# STM32F030.net
KiCad netlist of a schematic drawn in EAGLE
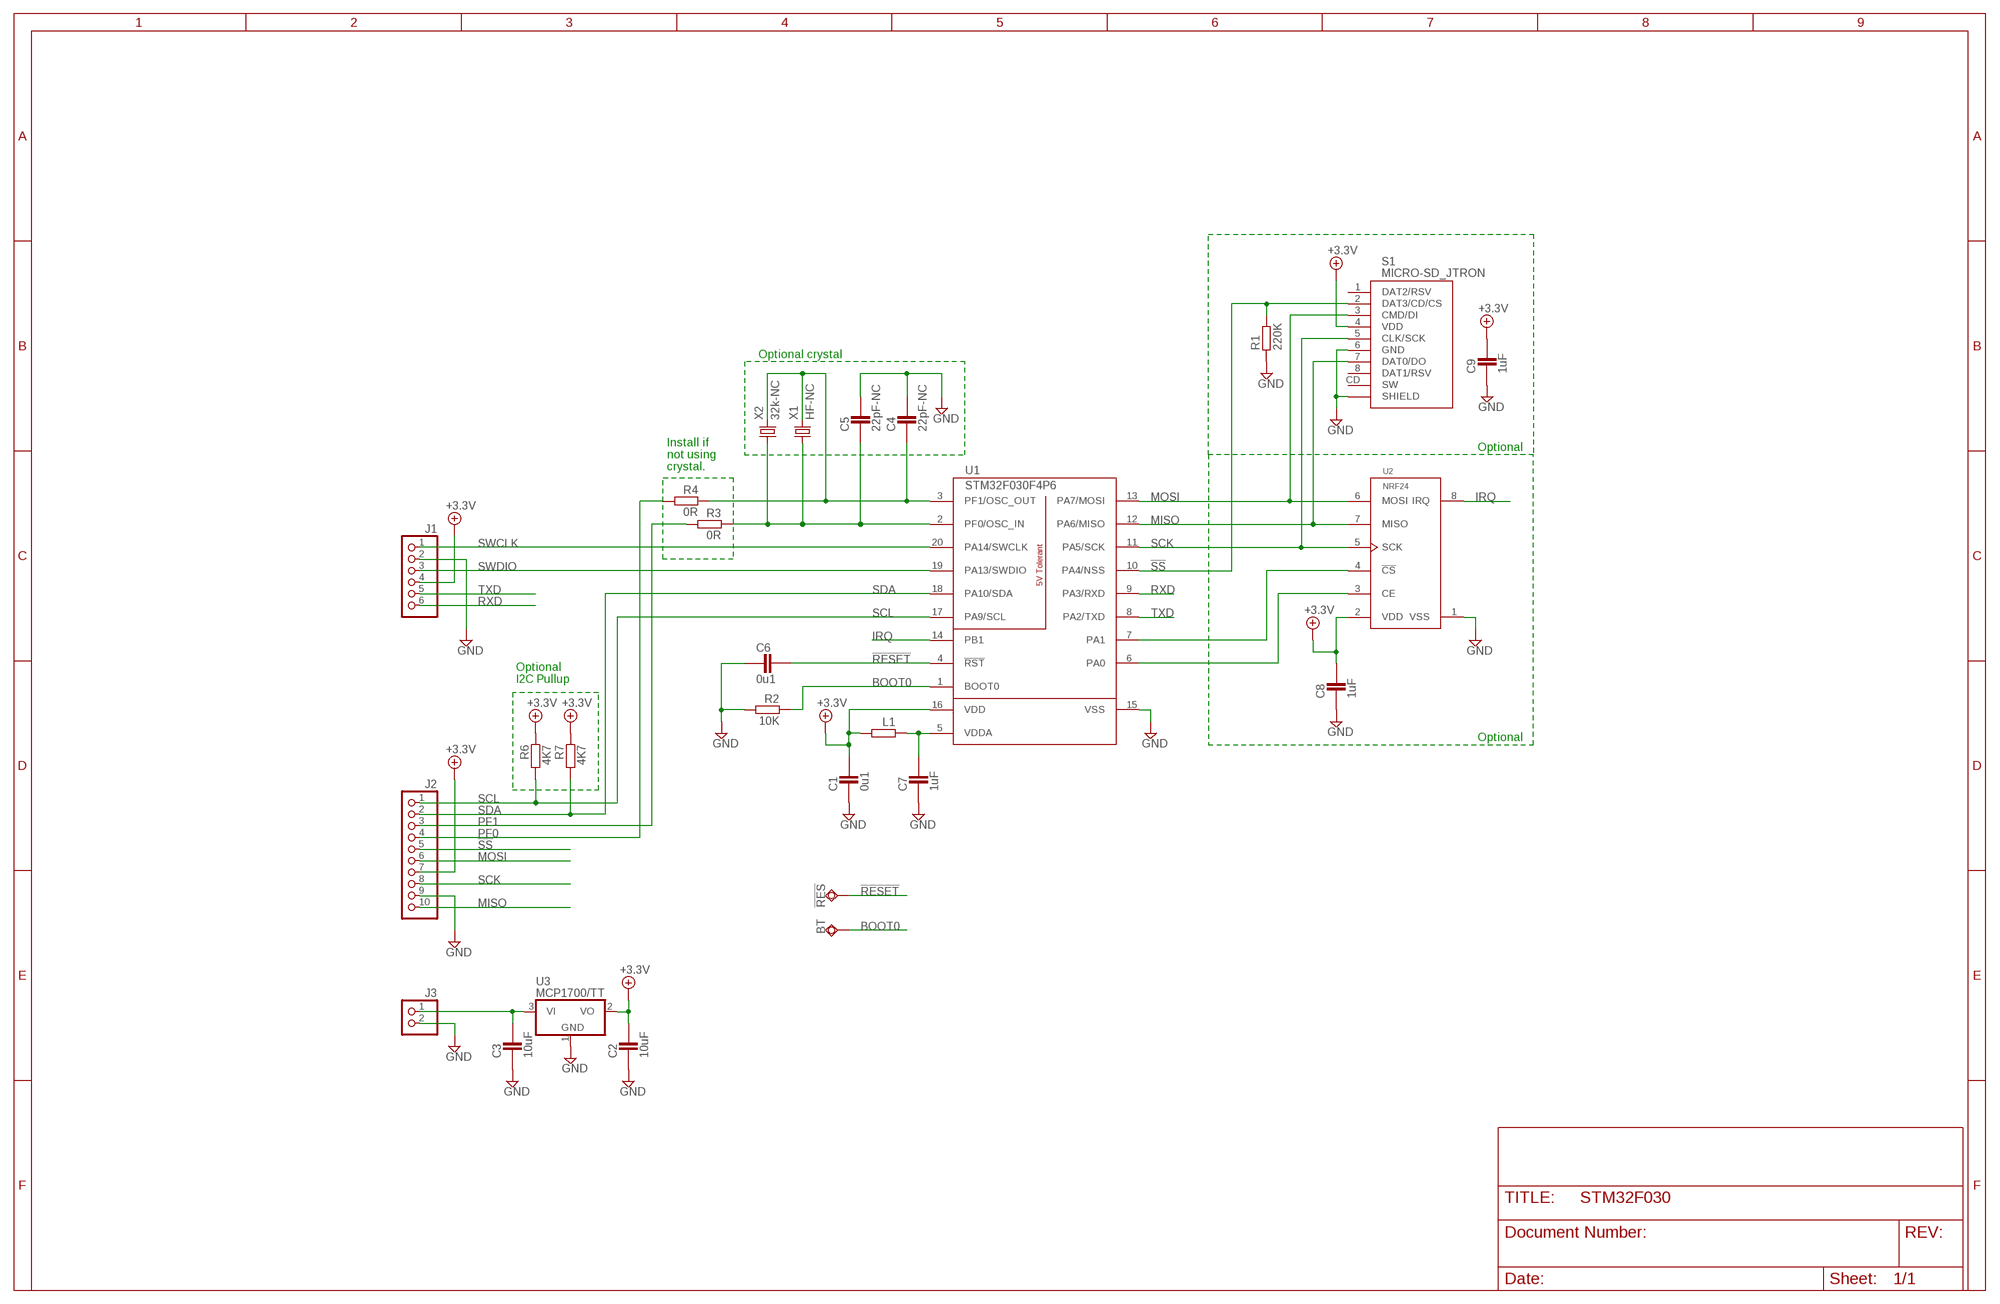
[diagram p0: schematic, sheet 1]

(export (version "E")
  (design (tool "Eeschema 10.0.6"))
  (components
    (comp (ref "!RES")
      (value "TPSQTP08SQ")
      (footprint "eagle-import:TP08SQ")
      (libsource (lib "eagle-import") (part "TPSQTP08SQ"))
    )
    (comp (ref "BT")
      (value "TPSQTP08SQ")
      (footprint "eagle-import:TP08SQ")
      (libsource (lib "eagle-import") (part "TPSQTP08SQ"))
    )
    (comp (ref "C1")
      (value "0u1")
      (footprint "eagle-import:CAPC1608X92N")
      (libsource (lib "eagle-import") (part "CAPACITOR_0603"))
    )
    (comp (ref "C2")
      (value "10uF")
      (footprint "eagle-import:CAPC2012X145AN")
      (libsource (lib "eagle-import") (part "CAPACITOR_0805"))
    )
    (comp (ref "C3")
      (value "10uF")
      (footprint "eagle-import:CAPC2012X145AN")
      (libsource (lib "eagle-import") (part "CAPACITOR_0805"))
    )
    (comp (ref "C4")
      (value "22pF-NC")
      (footprint "eagle-import:CAPC1608X92N")
      (libsource (lib "eagle-import") (part "CAPACITOR_0603"))
    )
    (comp (ref "C5")
      (value "22pF-NC")
      (footprint "eagle-import:CAPC1608X92N")
      (libsource (lib "eagle-import") (part "CAPACITOR_0603"))
    )
    (comp (ref "C6")
      (value "0u1")
      (footprint "eagle-import:CAPC1608X92N")
      (libsource (lib "eagle-import") (part "CAPACITOR_0603"))
    )
    (comp (ref "C7")
      (value "1uF")
      (footprint "eagle-import:CAPC1608X92N")
      (libsource (lib "eagle-import") (part "CAPACITOR_0603"))
    )
    (comp (ref "C8")
      (value "1uF")
      (footprint "eagle-import:CAPC1608X92N")
      (libsource (lib "eagle-import") (part "CAPACITOR_0603"))
    )
    (comp (ref "C9")
      (value "1uF")
      (footprint "eagle-import:CAPC1608X92N")
      (libsource (lib "eagle-import") (part "CAPACITOR_0603"))
    )
    (comp (ref "J1")
      (value "PINHD-1X6")
      (footprint "eagle-import:1X06")
      (libsource (lib "eagle-import") (part "PINHD-1X6"))
    )
    (comp (ref "J2")
      (value "PINHD-1X10")
      (footprint "eagle-import:1X10")
      (libsource (lib "eagle-import") (part "PINHD-1X10"))
    )
    (comp (ref "J3")
      (value "PINHD-1X2_2.54")
      (footprint "eagle-import:1X02")
      (libsource (lib "eagle-import") (part "PINHD-1X2_2.54"))
    )
    (comp (ref "L1")
      (value "RESISTOR_0603")
      (footprint "eagle-import:RESC1608X55N")
      (libsource (lib "eagle-import") (part "RESISTOR_0603"))
    )
    (comp (ref "R1")
      (value "220K")
      (footprint "eagle-import:RESC1608X55N")
      (libsource (lib "eagle-import") (part "RESISTOR_0603"))
    )
    (comp (ref "R2")
      (value "10K")
      (footprint "eagle-import:RESC1608X55N")
      (libsource (lib "eagle-import") (part "RESISTOR_0603"))
    )
    (comp (ref "R3")
      (value "0R")
      (footprint "eagle-import:RESC1608X55N")
      (libsource (lib "eagle-import") (part "RESISTOR_0603"))
    )
    (comp (ref "R4")
      (value "0R")
      (footprint "eagle-import:RESC1608X55N")
      (libsource (lib "eagle-import") (part "RESISTOR_0603"))
    )
    (comp (ref "R6")
      (value "4K7")
      (footprint "eagle-import:RESC1608X55N")
      (libsource (lib "eagle-import") (part "RESISTOR_0603"))
    )
    (comp (ref "R7")
      (value "4K7")
      (footprint "eagle-import:RESC1608X55N")
      (libsource (lib "eagle-import") (part "RESISTOR_0603"))
    )
    (comp (ref "S1")
      (value "MICRO-SD_JTRON")
      (footprint "eagle-import:JTRON-MICROSD")
      (libsource (lib "eagle-import") (part "MICRO-SD_JTRON"))
    )
    (comp (ref "U1")
      (value "STM32F030F4P6")
      (footprint "eagle-import:TSSOP20")
      (libsource (lib "eagle-import") (part "STM32F030F4P6"))
    )
    (comp (ref "U2")
      (value "NRF24")
      (footprint "eagle-import:NRF24L01")
      (libsource (lib "eagle-import") (part "NRF24"))
    )
    (comp (ref "U3")
      (value "MCP1700/TT")
      (footprint "eagle-import:SOT95P280X135-3N")
      (libsource (lib "eagle-import") (part "MCP1700/TT"))
    )
    (comp (ref "X1")
      (value "HF-NC")
      (footprint "eagle-import:SM49")
      (libsource (lib "eagle-import") (part "CRYSTALSM49"))
    )
    (comp (ref "X2")
      (value "32k-NC")
      (footprint "eagle-import:CRYSTAL32SMT")
      (libsource (lib "eagle-import") (part "CRYSTALWATCH"))
    )
  )
  (nets
    (net (code "1") (name "+3.3V") (class "Default")
      (node (ref "C1") (pin "2") (pinfunction "2_2") (pintype "passive"))
      (node (ref "C2") (pin "2") (pinfunction "2_2") (pintype "passive"))
      (node (ref "C8") (pin "2") (pinfunction "2_2") (pintype "passive"))
      (node (ref "C9") (pin "2") (pinfunction "2_2") (pintype "passive"))
      (node (ref "J1") (pin "4") (pinfunction "4_4") (pintype "passive"))
      (node (ref "J2") (pin "7") (pinfunction "7_7") (pintype "passive"))
      (node (ref "L1") (pin "2") (pinfunction "2_2") (pintype "passive"))
      (node (ref "R6") (pin "1") (pinfunction "1_1") (pintype "passive"))
      (node (ref "R7") (pin "1") (pinfunction "1_1") (pintype "passive"))
      (node (ref "S1") (pin "4") (pinfunction "VDD_4") (pintype "bidirectional"))
      (node (ref "U1") (pin "16") (pinfunction "VDD_16") (pintype "input"))
      (node (ref "U2") (pin "2") (pinfunction "VDD_2") (pintype "input"))
      (node (ref "U3") (pin "2") (pinfunction "VO_2") (pintype "passive"))
    )
    (net (code "2") (name "/BOOT0") (class "Default")
      (node (ref "BT") (pin "TP") (pinfunction "TP_TP") (pintype "input"))
      (node (ref "R2") (pin "1") (pinfunction "1_1") (pintype "passive"))
      (node (ref "U1") (pin "1") (pinfunction "BOOT0_1") (pintype "input"))
    )
    (net (code "3") (name "/IRQ") (class "Default")
      (node (ref "U1") (pin "14") (pinfunction "PB1_14") (pintype "bidirectional"))
      (node (ref "U2") (pin "8") (pinfunction "IRQ_8") (pintype "output"))
    )
    (net (code "4") (name "/MISO") (class "Default")
      (node (ref "J2") (pin "10") (pinfunction "10_10") (pintype "passive"))
      (node (ref "S1") (pin "7") (pinfunction "DAT0/DO_7") (pintype "bidirectional"))
      (node (ref "U1") (pin "12") (pinfunction "PA6/MISO_12") (pintype "bidirectional"))
      (node (ref "U2") (pin "7") (pinfunction "MISO_7") (pintype "output"))
    )
    (net (code "5") (name "/MOSI") (class "Default")
      (node (ref "J2") (pin "6") (pinfunction "6_6") (pintype "passive"))
      (node (ref "S1") (pin "3") (pinfunction "CMD/DI_3") (pintype "bidirectional"))
      (node (ref "U1") (pin "13") (pinfunction "PA7/MOSI_13") (pintype "bidirectional"))
      (node (ref "U2") (pin "6") (pinfunction "MOSI_6") (pintype "input"))
    )
    (net (code "7") (name "/PF0") (class "Default")
      (node (ref "J2") (pin "4") (pinfunction "4_4") (pintype "passive"))
      (node (ref "R4") (pin "2") (pinfunction "2_2") (pintype "passive"))
    )
    (net (code "8") (name "/PF1") (class "Default")
      (node (ref "J2") (pin "3") (pinfunction "3_3") (pintype "passive"))
      (node (ref "R3") (pin "2") (pinfunction "2_2") (pintype "passive"))
    )
    (net (code "9") (name "/RXD") (class "Default")
      (node (ref "J1") (pin "6") (pinfunction "6_6") (pintype "passive"))
      (node (ref "U1") (pin "9") (pinfunction "PA3/RXD_9") (pintype "bidirectional"))
    )
    (net (code "10") (name "/SCK") (class "Default")
      (node (ref "J2") (pin "8") (pinfunction "8_8") (pintype "passive"))
      (node (ref "S1") (pin "5") (pinfunction "CLK/SCK_5") (pintype "bidirectional"))
      (node (ref "U1") (pin "11") (pinfunction "PA5/SCK_11") (pintype "bidirectional"))
      (node (ref "U2") (pin "5") (pinfunction "SCK_5") (pintype "input"))
    )
    (net (code "11") (name "/SCL") (class "Default")
      (node (ref "J2") (pin "1") (pinfunction "1_1") (pintype "passive"))
      (node (ref "R6") (pin "2") (pinfunction "2_2") (pintype "passive"))
      (node (ref "U1") (pin "17") (pinfunction "PA9/SCL_17") (pintype "bidirectional"))
    )
    (net (code "12") (name "/SDA") (class "Default")
      (node (ref "J2") (pin "2") (pinfunction "2_2") (pintype "passive"))
      (node (ref "R7") (pin "2") (pinfunction "2_2") (pintype "passive"))
      (node (ref "U1") (pin "18") (pinfunction "PA10/SDA_18") (pintype "bidirectional"))
    )
    (net (code "13") (name "/SWCLK") (class "Default")
      (node (ref "J1") (pin "1") (pinfunction "1_1") (pintype "passive"))
      (node (ref "U1") (pin "20") (pinfunction "PA14/SWCLK_20") (pintype "bidirectional"))
    )
    (net (code "14") (name "/SWDIO") (class "Default")
      (node (ref "J1") (pin "3") (pinfunction "3_3") (pintype "passive"))
      (node (ref "U1") (pin "19") (pinfunction "PA13/SWDIO_19") (pintype "bidirectional"))
    )
    (net (code "15") (name "/TXD") (class "Default")
      (node (ref "J1") (pin "5") (pinfunction "5_5") (pintype "passive"))
      (node (ref "U1") (pin "8") (pinfunction "PA2/TXD_8") (pintype "bidirectional"))
    )
    (net (code "16") (name "/~{RESET}") (class "Default")
      (node (ref "!RES") (pin "TP") (pinfunction "TP_TP") (pintype "input"))
      (node (ref "C6") (pin "2") (pinfunction "2_2") (pintype "passive"))
      (node (ref "U1") (pin "4") (pinfunction "~{RST}_4") (pintype "input"))
    )
    (net (code "17") (name "/~{SS}") (class "Default")
      (node (ref "J2") (pin "5") (pinfunction "5_5") (pintype "passive"))
      (node (ref "R1") (pin "2") (pinfunction "2_2") (pintype "passive"))
      (node (ref "S1") (pin "2") (pinfunction "DAT3/CD/CS_2") (pintype "bidirectional"))
      (node (ref "U1") (pin "10") (pinfunction "PA4/NSS_10") (pintype "bidirectional"))
    )
    (net (code "18") (name "GND") (class "Default")
      (node (ref "C1") (pin "1") (pinfunction "1_1") (pintype "passive"))
      (node (ref "C2") (pin "1") (pinfunction "1_1") (pintype "passive"))
      (node (ref "C3") (pin "1") (pinfunction "1_1") (pintype "passive"))
      (node (ref "C4") (pin "2") (pinfunction "2_2") (pintype "passive"))
      (node (ref "C5") (pin "2") (pinfunction "2_2") (pintype "passive"))
      (node (ref "C6") (pin "1") (pinfunction "1_1") (pintype "passive"))
      (node (ref "C7") (pin "1") (pinfunction "1_1") (pintype "passive"))
      (node (ref "C8") (pin "1") (pinfunction "1_1") (pintype "passive"))
      (node (ref "C9") (pin "1") (pinfunction "1_1") (pintype "passive"))
      (node (ref "J1") (pin "2") (pinfunction "2_2") (pintype "passive"))
      (node (ref "J2") (pin "9") (pinfunction "9_9") (pintype "passive"))
      (node (ref "J3") (pin "2") (pinfunction "2_2") (pintype "passive"))
      (node (ref "R1") (pin "1") (pinfunction "1_1") (pintype "passive"))
      (node (ref "R2") (pin "2") (pinfunction "2_2") (pintype "passive"))
      (node (ref "S1") (pin "6") (pinfunction "GND_6") (pintype "bidirectional"))
      (node (ref "S1") (pin "SHIELD@1") (pinfunction "SHIELD_SHIELD@1") (pintype "bidirectional"))
      (node (ref "S1") (pin "SHIELD@2") (pinfunction "SHIELD_SHIELD@2") (pintype "bidirectional"))
      (node (ref "S1") (pin "SHIELD@3") (pinfunction "SHIELD_SHIELD@3") (pintype "bidirectional"))
      (node (ref "S1") (pin "SHIELD@4") (pinfunction "SHIELD_SHIELD@4") (pintype "bidirectional"))
      (node (ref "U1") (pin "15") (pinfunction "VSS_15") (pintype "input"))
      (node (ref "U2") (pin "1") (pinfunction "VSS_1") (pintype "input"))
      (node (ref "U3") (pin "1") (pinfunction "GND_1") (pintype "passive"))
    )
    (net (code "19") (name "Net-(U1-PA0)") (class "Default")
      (node (ref "U1") (pin "6") (pinfunction "PA0_6") (pintype "bidirectional"))
      (node (ref "U2") (pin "3") (pinfunction "CE_3") (pintype "input"))
    )
    (net (code "20") (name "Net-(U1-PA1)") (class "Default")
      (node (ref "U1") (pin "7") (pinfunction "PA1_7") (pintype "bidirectional"))
      (node (ref "U2") (pin "4") (pinfunction "~{CS}_4") (pintype "input"))
    )
    (net (code "21") (name "Net-(U1-PF0{slash}OSC_IN)") (class "Default")
      (node (ref "C5") (pin "1") (pinfunction "1_1") (pintype "passive"))
      (node (ref "R3") (pin "1") (pinfunction "1_1") (pintype "passive"))
      (node (ref "U1") (pin "2") (pinfunction "PF0/OSC_IN_2") (pintype "input"))
      (node (ref "X1") (pin "1") (pinfunction "1_1") (pintype "passive"))
      (node (ref "X2") (pin "1") (pinfunction "1_1") (pintype "passive"))
    )
    (net (code "22") (name "Net-(U1-PF1{slash}OSC_OUT)") (class "Default")
      (node (ref "C4") (pin "1") (pinfunction "1_1") (pintype "passive"))
      (node (ref "R4") (pin "1") (pinfunction "1_1") (pintype "passive"))
      (node (ref "U1") (pin "3") (pinfunction "PF1/OSC_OUT_3") (pintype "output"))
      (node (ref "X1") (pin "2") (pinfunction "2_2") (pintype "passive"))
      (node (ref "X2") (pin "2") (pinfunction "2_2") (pintype "passive"))
    )
    (net (code "23") (name "Net-(U1-VDDA)") (class "Default")
      (node (ref "C7") (pin "2") (pinfunction "2_2") (pintype "passive"))
      (node (ref "L1") (pin "1") (pinfunction "1_1") (pintype "passive"))
      (node (ref "U1") (pin "5") (pinfunction "VDDA_5") (pintype "input"))
    )
    (net (code "24") (name "Net-(U3-VI)") (class "Default")
      (node (ref "C3") (pin "2") (pinfunction "2_2") (pintype "passive"))
      (node (ref "J3") (pin "1") (pinfunction "1_1") (pintype "passive"))
      (node (ref "U3") (pin "3") (pinfunction "VI_3") (pintype "input"))
    )
    (net (code "25") (name "unconnected-(S1-DAT1{slash}RSV-Pad8)") (class "Default")
      (node (ref "S1") (pin "8") (pinfunction "DAT1/RSV_8") (pintype "bidirectional"))
    )
    (net (code "26") (name "unconnected-(S1-DAT2{slash}RSV-Pad1)") (class "Default")
      (node (ref "S1") (pin "1") (pinfunction "DAT2/RSV_1") (pintype "bidirectional"))
    )
    (net (code "27") (name "unconnected-(S1-SW-PadCD)") (class "Default")
      (node (ref "S1") (pin "CD") (pinfunction "SW_CD") (pintype "bidirectional"))
    )
  )
)
